# 2out_16A_bi_TS_V0_2.net
KiCad netlist of a schematic drawn in EAGLE
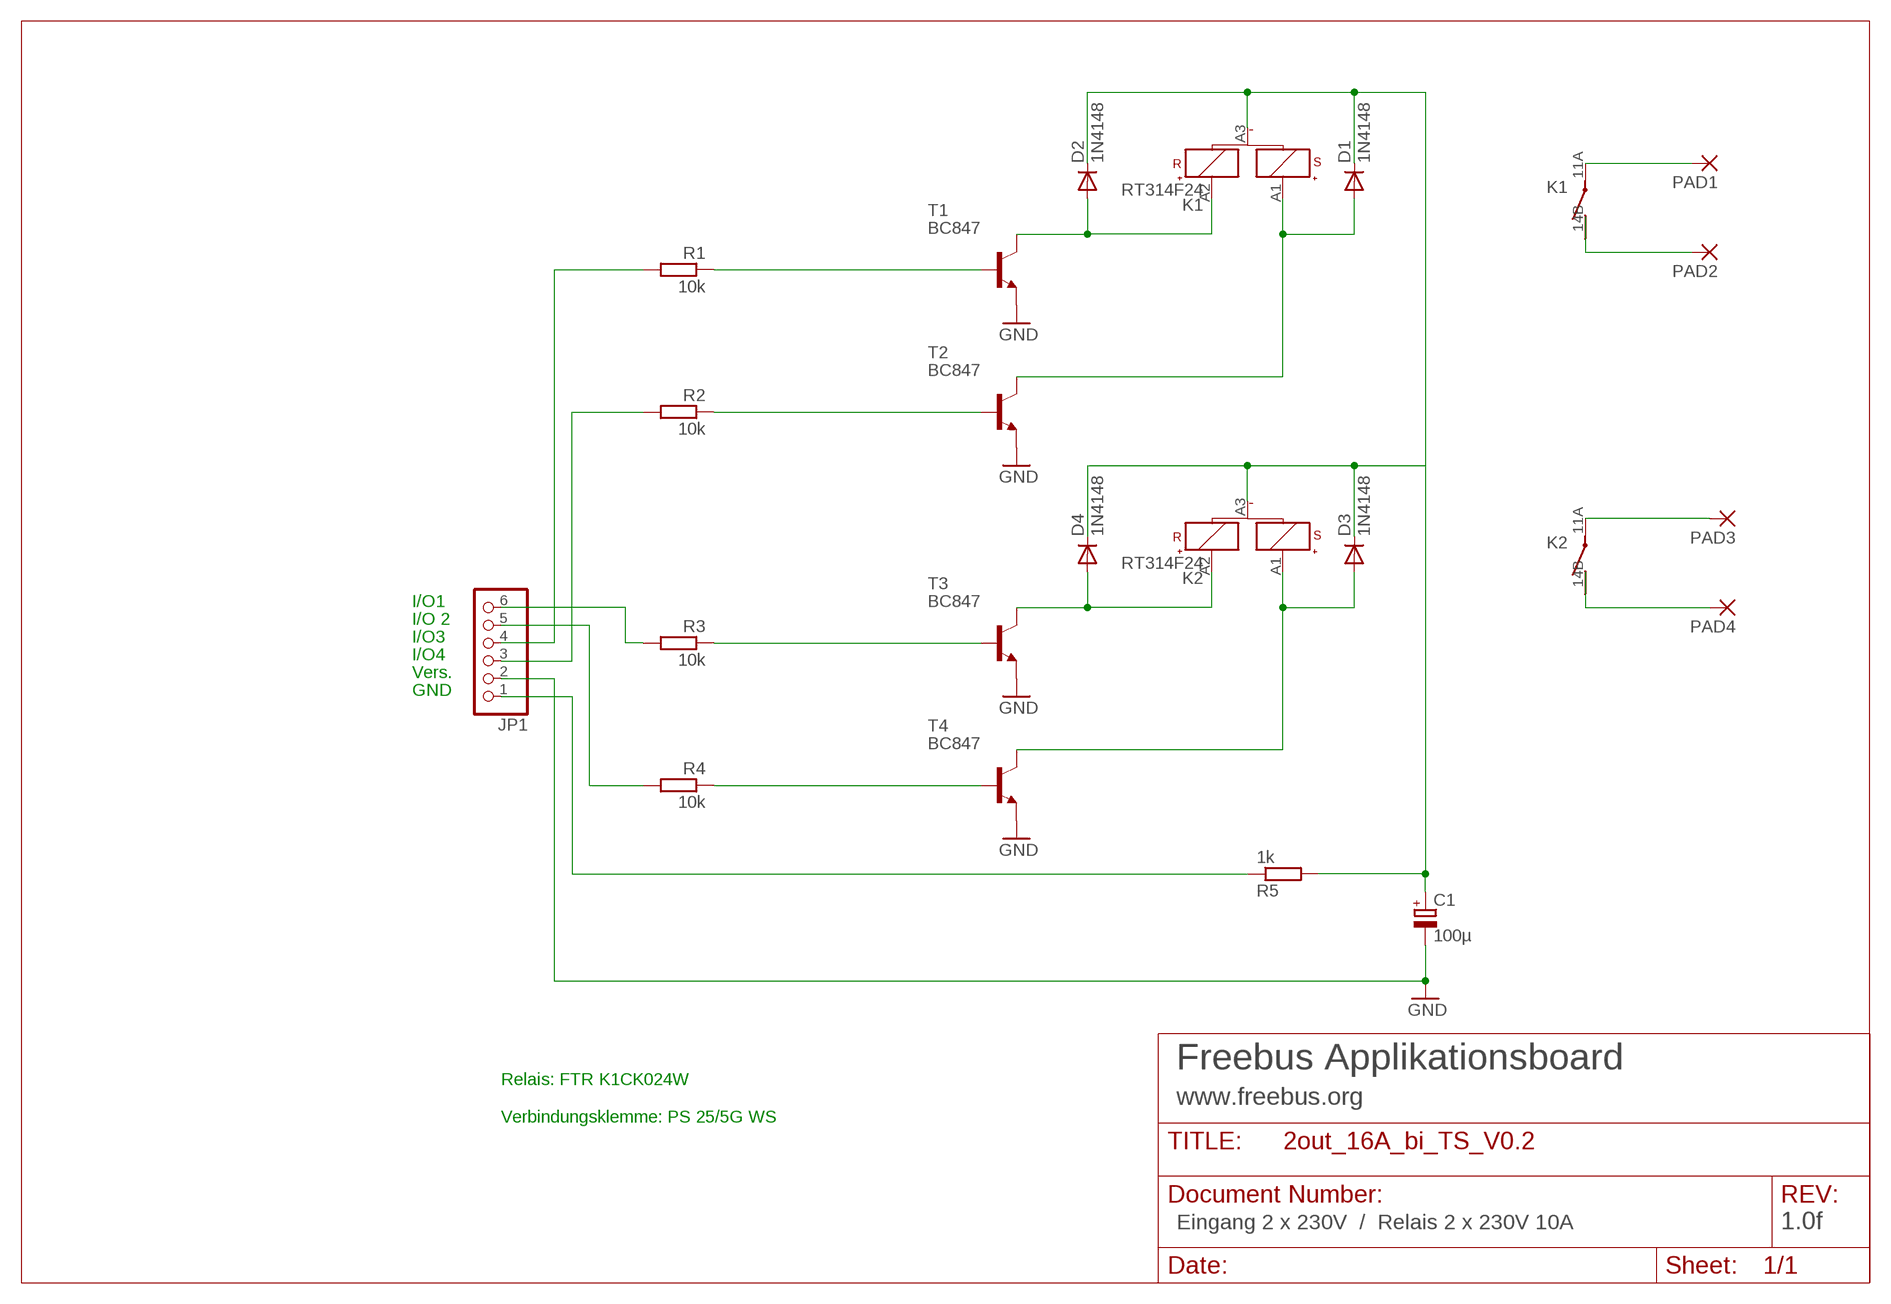
[diagram p0: schematic, sheet 1]

(export (version "E")
  (design (tool "Eeschema 10.0.6"))
  (components
    (comp (ref "C1")
      (value "100µ")
      (footprint "eagle-import:E3,5-8")
      (libsource (lib "eagle-import") (part "CPOL-EUE3.5-8"))
    )
    (comp (ref "D1")
      (value "1N4148")
      (footprint "eagle-import:MINIMELF")
      (libsource (lib "eagle-import") (part "DIODE-MINIMELF"))
    )
    (comp (ref "D2")
      (value "1N4148")
      (footprint "eagle-import:MINIMELF")
      (libsource (lib "eagle-import") (part "DIODE-MINIMELF"))
    )
    (comp (ref "D3")
      (value "1N4148")
      (footprint "eagle-import:MINIMELF")
      (libsource (lib "eagle-import") (part "DIODE-MINIMELF"))
    )
    (comp (ref "D4")
      (value "1N4148")
      (footprint "eagle-import:MINIMELF")
      (libsource (lib "eagle-import") (part "DIODE-MINIMELF"))
    )
    (comp (ref "JP1")
      (value "PINHD-1X6/90")
      (footprint "eagle-import:1X06_90")
      (libsource (lib "eagle-import") (part "PINHD-1X6/90"))
    )
    (comp (ref "K1")
      (value "RT314F24")
      (footprint "eagle-import:RT1-BI")
      (libsource (lib "eagle-import") (part "RT?F31424"))
    )
    (comp (ref "K2")
      (value "RT314F24")
      (footprint "eagle-import:RT1-BI")
      (libsource (lib "eagle-import") (part "RT?F31424"))
    )
    (comp (ref "PAD1")
      (value "3,81/1,4")
      (footprint "eagle-import:3,81_1,4")
      (libsource (lib "eagle-import") (part "3,81/1,4"))
    )
    (comp (ref "PAD2")
      (value "3,81/1,4")
      (footprint "eagle-import:3,81_1,4")
      (libsource (lib "eagle-import") (part "3,81/1,4"))
    )
    (comp (ref "PAD3")
      (value "3,81/1,4")
      (footprint "eagle-import:3,81_1,4")
      (libsource (lib "eagle-import") (part "3,81/1,4"))
    )
    (comp (ref "PAD4")
      (value "3,81/1,4")
      (footprint "eagle-import:3,81_1,4")
      (libsource (lib "eagle-import") (part "3,81/1,4"))
    )
    (comp (ref "R1")
      (value "10k")
      (footprint "eagle-import:M1206")
      (libsource (lib "eagle-import") (part "R-EU_M1206"))
    )
    (comp (ref "R2")
      (value "10k")
      (footprint "eagle-import:M1206")
      (libsource (lib "eagle-import") (part "R-EU_M1206"))
    )
    (comp (ref "R3")
      (value "10k")
      (footprint "eagle-import:M1206")
      (libsource (lib "eagle-import") (part "R-EU_M1206"))
    )
    (comp (ref "R4")
      (value "10k")
      (footprint "eagle-import:M1206")
      (libsource (lib "eagle-import") (part "R-EU_M1206"))
    )
    (comp (ref "R5")
      (value "1k")
      (footprint "eagle-import:M1206")
      (libsource (lib "eagle-import") (part "R-EU_M1206"))
    )
    (comp (ref "T1")
      (value "BC847")
      (footprint "eagle-import:SOT23")
      (libsource (lib "eagle-import") (part "BC847"))
    )
    (comp (ref "T2")
      (value "BC847")
      (footprint "eagle-import:SOT23")
      (libsource (lib "eagle-import") (part "BC847"))
    )
    (comp (ref "T3")
      (value "BC847")
      (footprint "eagle-import:SOT23")
      (libsource (lib "eagle-import") (part "BC847"))
    )
    (comp (ref "T4")
      (value "BC847")
      (footprint "eagle-import:SOT23")
      (libsource (lib "eagle-import") (part "BC847"))
    )
  )
  (nets
    (net (code "1") (name "GND") (class "Default")
      (node (ref "C1") (pin "-") (pinfunction "-_-") (pintype "passive"))
      (node (ref "JP1") (pin "2") (pinfunction "2_2") (pintype "passive"))
      (node (ref "T1") (pin "2") (pinfunction "E_2") (pintype "passive"))
      (node (ref "T2") (pin "2") (pinfunction "E_2") (pintype "passive"))
      (node (ref "T3") (pin "2") (pinfunction "E_2") (pintype "passive"))
      (node (ref "T4") (pin "2") (pinfunction "E_2") (pintype "passive"))
    )
    (net (code "2") (name "Net-(JP1-Pad1)") (class "Default")
      (node (ref "JP1") (pin "1") (pinfunction "1_1") (pintype "passive"))
      (node (ref "R5") (pin "1") (pinfunction "1_1") (pintype "passive"))
    )
    (net (code "3") (name "Net-(JP1-Pad3)") (class "Default")
      (node (ref "JP1") (pin "3") (pinfunction "3_3") (pintype "passive"))
      (node (ref "R2") (pin "2") (pinfunction "2_2") (pintype "passive"))
    )
    (net (code "4") (name "Net-(JP1-Pad4)") (class "Default")
      (node (ref "JP1") (pin "4") (pinfunction "4_4") (pintype "passive"))
      (node (ref "R1") (pin "2") (pinfunction "2_2") (pintype "passive"))
    )
    (net (code "5") (name "Net-(JP1-Pad5)") (class "Default")
      (node (ref "JP1") (pin "5") (pinfunction "5_5") (pintype "passive"))
      (node (ref "R4") (pin "2") (pinfunction "2_2") (pintype "passive"))
    )
    (net (code "6") (name "Net-(JP1-Pad6)") (class "Default")
      (node (ref "JP1") (pin "6") (pinfunction "6_6") (pintype "passive"))
      (node (ref "R3") (pin "2") (pinfunction "2_2") (pintype "passive"))
    )
    (net (code "7") (name "Net-(K1A--)") (class "Default")
      (node (ref "C1") (pin "+") (pinfunction "+_+") (pintype "passive"))
      (node (ref "D1") (pin "C") (pinfunction "C_C") (pintype "passive"))
      (node (ref "D2") (pin "C") (pinfunction "C_C") (pintype "passive"))
      (node (ref "D3") (pin "C") (pinfunction "C_C") (pintype "passive"))
      (node (ref "D4") (pin "C") (pinfunction "C_C") (pintype "passive"))
      (node (ref "K1") (pin "A3") (pinfunction "-_A3") (pintype "passive"))
      (node (ref "K2") (pin "A3") (pinfunction "-_A3") (pintype "passive"))
      (node (ref "R5") (pin "2") (pinfunction "2_2") (pintype "passive"))
    )
    (net (code "8") (name "Net-(K1A-R+)") (class "Default")
      (node (ref "D2") (pin "A") (pinfunction "A_A") (pintype "passive"))
      (node (ref "K1") (pin "A2") (pinfunction "R+_A2") (pintype "passive"))
      (node (ref "T1") (pin "3") (pinfunction "C_3") (pintype "passive"))
    )
    (net (code "9") (name "Net-(K1A-S+)") (class "Default")
      (node (ref "D1") (pin "A") (pinfunction "A_A") (pintype "passive"))
      (node (ref "K1") (pin "A1") (pinfunction "S+_A1") (pintype "passive"))
      (node (ref "T2") (pin "3") (pinfunction "C_3") (pintype "passive"))
    )
    (net (code "10") (name "Net-(K1B-PA)") (class "Default")
      (node (ref "K1") (pin "11A") (pinfunction "PA_11A") (pintype "passive"))
      (node (ref "PAD1") (pin "1") (pinfunction "P_1") (pintype "passive"))
    )
    (net (code "11") (name "Net-(K1B-SA)") (class "Default")
      (node (ref "K1") (pin "14B") (pinfunction "SA_14B") (pintype "passive"))
      (node (ref "PAD2") (pin "1") (pinfunction "P_1") (pintype "passive"))
    )
    (net (code "12") (name "Net-(K2A-R+)") (class "Default")
      (node (ref "D4") (pin "A") (pinfunction "A_A") (pintype "passive"))
      (node (ref "K2") (pin "A2") (pinfunction "R+_A2") (pintype "passive"))
      (node (ref "T3") (pin "3") (pinfunction "C_3") (pintype "passive"))
    )
    (net (code "13") (name "Net-(K2A-S+)") (class "Default")
      (node (ref "D3") (pin "A") (pinfunction "A_A") (pintype "passive"))
      (node (ref "K2") (pin "A1") (pinfunction "S+_A1") (pintype "passive"))
      (node (ref "T4") (pin "3") (pinfunction "C_3") (pintype "passive"))
    )
    (net (code "14") (name "Net-(K2B-PA)") (class "Default")
      (node (ref "K2") (pin "11A") (pinfunction "PA_11A") (pintype "passive"))
      (node (ref "PAD3") (pin "1") (pinfunction "P_1") (pintype "passive"))
    )
    (net (code "15") (name "Net-(K2B-SA)") (class "Default")
      (node (ref "K2") (pin "14B") (pinfunction "SA_14B") (pintype "passive"))
      (node (ref "PAD4") (pin "1") (pinfunction "P_1") (pintype "passive"))
    )
    (net (code "16") (name "Net-(T1-B)") (class "Default")
      (node (ref "R1") (pin "1") (pinfunction "1_1") (pintype "passive"))
      (node (ref "T1") (pin "1") (pinfunction "B_1") (pintype "passive"))
    )
    (net (code "17") (name "Net-(T2-B)") (class "Default")
      (node (ref "R2") (pin "1") (pinfunction "1_1") (pintype "passive"))
      (node (ref "T2") (pin "1") (pinfunction "B_1") (pintype "passive"))
    )
    (net (code "18") (name "Net-(T3-B)") (class "Default")
      (node (ref "R3") (pin "1") (pinfunction "1_1") (pintype "passive"))
      (node (ref "T3") (pin "1") (pinfunction "B_1") (pintype "passive"))
    )
    (net (code "19") (name "Net-(T4-B)") (class "Default")
      (node (ref "R4") (pin "1") (pinfunction "1_1") (pintype "passive"))
      (node (ref "T4") (pin "1") (pinfunction "B_1") (pintype "passive"))
    )
  )
)
